# Filtre_PWM1kHz.net
KiCad netlist of a schematic drawn in Altium Designer
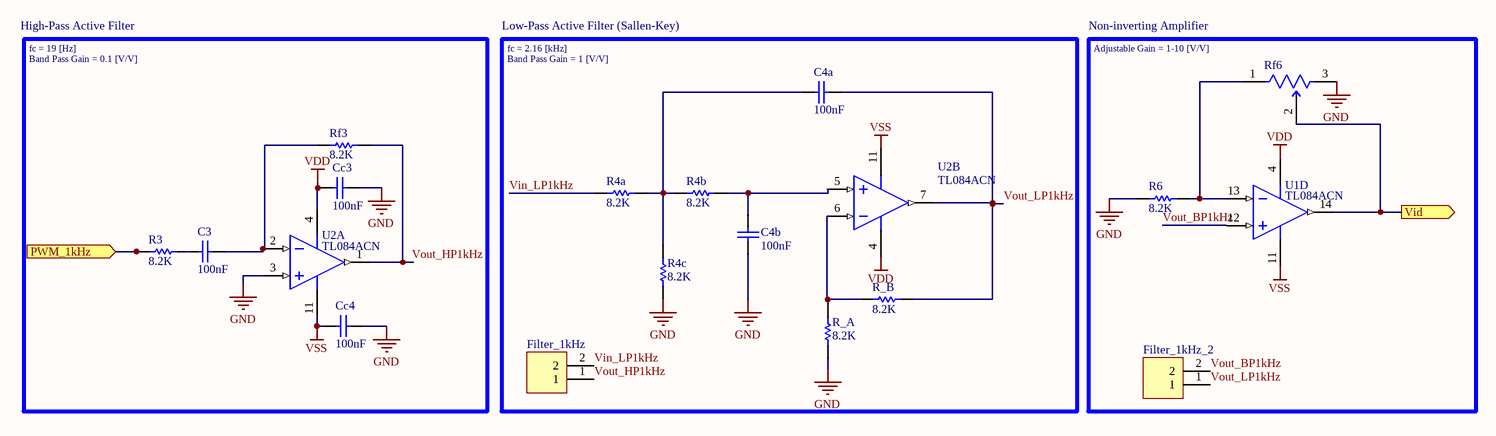
[diagram p0: Filtre_PWM1kHz.SchDoc]

(export (version "E")
  (design (tool "Eeschema 10.0.6"))
  (components
    (comp (ref "C3")
      (value "100nF")
      (footprint "condensateur 0.1uf 100mil")
      (description "Capacitor")
      (fields (field (name "Comment") "Cap") (field (name "PUBLISHER") "Altium Limited"))
      (libsource (lib "signal-generator") (part "Cap"))
    )
    (comp (ref "C4a")
      (value "100nF")
      (footprint "condensateur 0.1uf 100mil")
      (description "Capacitor")
      (fields (field (name "Comment") "Cap") (field (name "PUBLISHER") "Altium Limited"))
      (libsource (lib "signal-generator") (part "Cap"))
    )
    (comp (ref "C4b")
      (value "100nF")
      (footprint "condensateur 0.1uf 100mil")
      (description "Capacitor")
      (fields (field (name "Comment") "Cap") (field (name "PUBLISHER") "Altium Limited"))
      (libsource (lib "signal-generator") (part "Cap"))
    )
    (comp (ref "Cc3")
      (value "100nF")
      (footprint "condensateur 0.1uf 100mil")
      (description "Capacitor")
      (fields (field (name "Comment") "Cap") (field (name "PUBLISHER") "Altium Limited"))
      (libsource (lib "signal-generator") (part "Cap"))
    )
    (comp (ref "Cc4")
      (value "100nF")
      (footprint "condensateur 0.1uf 100mil")
      (description "Capacitor")
      (fields (field (name "Comment") "Cap") (field (name "PUBLISHER") "Altium Limited"))
      (libsource (lib "signal-generator") (part "Cap"))
    )
    (comp (ref "Filter_1kHz")
      (value "Jumper")
      (footprint "Header 2P 100mil")
      (description "CONN HEADER VERT 3POS 2.54MM")
      (fields (field (name "PUBLISHER") "Altium Limited"))
      (libsource (lib "PCB_Alimentation_équipe1") (part "header 2 pin_UL"))
    )
    (comp (ref "Filter_1kHz_2")
      (value "Jumper")
      (footprint "Header 2P 100mil")
      (description "CONN HEADER VERT 3POS 2.54MM")
      (fields (field (name "PUBLISHER") "Altium Limited"))
      (libsource (lib "PCB_Alimentation_équipe1") (part "header 2 pin_UL"))
    )
    (comp (ref "R3")
      (value "8.2K")
      (footprint "Resistor_Axial 0.4")
      (description "Resistor")
      (fields (field (name "Comment") "Res1") (field (name "PUBLISHER") "Altium Limited"))
      (libsource (lib "signal-generator") (part "Res1"))
    )
    (comp (ref "R4a")
      (value "8.2K")
      (footprint "Resistor_Axial 0.4")
      (description "Resistor")
      (fields (field (name "Comment") "Res1") (field (name "PUBLISHER") "Altium Limited"))
      (libsource (lib "signal-generator") (part "Res1"))
    )
    (comp (ref "R4b")
      (value "8.2K")
      (footprint "Resistor_Axial 0.4")
      (description "Resistor")
      (fields (field (name "Comment") "Res1") (field (name "PUBLISHER") "Altium Limited"))
      (libsource (lib "signal-generator") (part "Res1"))
    )
    (comp (ref "R4c")
      (value "8.2K")
      (footprint "Resistor_Axial 0.4")
      (description "Resistor")
      (fields (field (name "Comment") "Res1") (field (name "PUBLISHER") "Altium Limited"))
      (libsource (lib "signal-generator") (part "Res1"))
    )
    (comp (ref "R6")
      (value "8.2K")
      (footprint "Resistor_Axial 0.4")
      (description "Resistor")
      (fields (field (name "Comment") "Res1") (field (name "PUBLISHER") "Altium Limited"))
      (libsource (lib "signal-generator") (part "Res1"))
    )
    (comp (ref "Rf3")
      (value "8.2K")
      (footprint "Resistor_Axial 0.4")
      (description "Resistor")
      (fields (field (name "Comment") "Res1") (field (name "PUBLISHER") "Altium Limited"))
      (libsource (lib "signal-generator") (part "Res1"))
    )
    (comp (ref "Rf6")
      (value "67WR100KLF")
      (footprint "FP-67W-MFG")
      (description "TRIMMER 100K OHM 0.5W PC PIN TOP")
      (fields (field (name "TOLERANCE") "10%"))
      (libsource (lib "Altium Content Vault") (part "a77ee20e32664c43a3a1dd5392b6021"))
    )
    (comp (ref "R_A")
      (value "8.2K")
      (footprint "Resistor_Axial 0.4")
      (description "Resistor")
      (fields (field (name "Comment") "Res1") (field (name "PUBLISHER") "Altium Limited"))
      (libsource (lib "signal-generator") (part "Res1"))
    )
    (comp (ref "R_B")
      (value "8.2K")
      (footprint "Resistor_Axial 0.4")
      (description "Resistor")
      (fields (field (name "Comment") "Res1") (field (name "PUBLISHER") "Altium Limited"))
      (libsource (lib "signal-generator") (part "Res1"))
    )
    (comp (ref "U1")
      (value "TL084ACN")
      (footprint "N0014A")
      (description "JFET-Input Operational Amplifier, 7 to 36 V, 0 to 70 degC, 14-pin DIP (N14), Pb-Free (RoHS)")
      (fields (field (name "MANUFACTURER") "Texas Instruments"))
      (libsource (lib "Altium Content Vault") (part "TI-TLXX4X_MC3403-X14"))
    )
    (comp (ref "U2")
      (value "TL084ACN")
      (footprint "N0014A")
      (description "JFET-Input Operational Amplifier, 7 to 36 V, 0 to 70 degC, 14-pin DIP (N14), Pb-Free (RoHS)")
      (fields (field (name "MANUFACTURER") "Texas Instruments"))
      (libsource (lib "Altium Content Vault") (part "TI-TLXX4X_MC3403-X14"))
    )
  )
  (nets
    (net (code "1") (name "/PWM_1kHz") (class "Default")
      (node (ref "R3") (pin "1") (pinfunction "1_1") (pintype "passive"))
    )
    (net (code "2") (name "/Vid") (class "Default")
      (node (ref "Rf6") (pin "2") (pinfunction "2_2") (pintype "passive"))
      (node (ref "U1") (pin "14") (pinfunction "OUT4_14") (pintype "output"))
    )
    (net (code "3") (name "/Vin_LP1kHz") (class "Default")
      (node (ref "Filter_1kHz") (pin "2") (pinfunction "2_2") (pintype "passive"))
      (node (ref "R4a") (pin "1") (pinfunction "1_1") (pintype "passive"))
    )
    (net (code "4") (name "/Vout_BP1kHz") (class "Default")
      (node (ref "Filter_1kHz_2") (pin "2") (pinfunction "2_2") (pintype "passive"))
      (node (ref "U1") (pin "12") (pinfunction "IN4+_12") (pintype "input"))
    )
    (net (code "5") (name "/Vout_HP1kHz") (class "Default")
      (node (ref "Filter_1kHz") (pin "1") (pinfunction "1_1") (pintype "passive"))
      (node (ref "Rf3") (pin "2") (pinfunction "2_2") (pintype "passive"))
      (node (ref "U2") (pin "1") (pinfunction "OUT1_1") (pintype "output"))
    )
    (net (code "6") (name "/Vout_LP1kHz") (class "Default")
      (node (ref "C4a") (pin "1") (pinfunction "1_1") (pintype "passive"))
      (node (ref "Filter_1kHz_2") (pin "1") (pinfunction "1_1") (pintype "passive"))
      (node (ref "R_B") (pin "2") (pinfunction "2_2") (pintype "passive"))
      (node (ref "U2") (pin "7") (pinfunction "OUT2_7") (pintype "output"))
    )
    (net (code "7") (name "GND") (class "Default")
      (node (ref "C4b") (pin "1") (pinfunction "1_1") (pintype "passive"))
      (node (ref "Cc3") (pin "2") (pinfunction "2_2") (pintype "passive"))
      (node (ref "Cc4") (pin "2") (pinfunction "2_2") (pintype "passive"))
      (node (ref "R4c") (pin "1") (pinfunction "1_1") (pintype "passive"))
      (node (ref "R6") (pin "1") (pinfunction "1_1") (pintype "passive"))
      (node (ref "R_A") (pin "1") (pinfunction "1_1") (pintype "passive"))
      (node (ref "Rf6") (pin "3") (pinfunction "3_3") (pintype "passive"))
      (node (ref "U2") (pin "3") (pinfunction "IN1+_3") (pintype "input"))
    )
    (net (code "8") (name "Net-(C3-Pad1)") (class "Default")
      (node (ref "C3") (pin "1") (pinfunction "1_1") (pintype "passive"))
      (node (ref "R3") (pin "2") (pinfunction "2_2") (pintype "passive"))
    )
    (net (code "9") (name "Net-(C4a-Pad2)") (class "Default")
      (node (ref "C4a") (pin "2") (pinfunction "2_2") (pintype "passive"))
      (node (ref "R4a") (pin "2") (pinfunction "2_2") (pintype "passive"))
      (node (ref "R4b") (pin "1") (pinfunction "1_1") (pintype "passive"))
      (node (ref "R4c") (pin "2") (pinfunction "2_2") (pintype "passive"))
    )
    (net (code "10") (name "Net-(U1D-IN4-)") (class "Default")
      (node (ref "R6") (pin "2") (pinfunction "2_2") (pintype "passive"))
      (node (ref "Rf6") (pin "1") (pinfunction "1_1") (pintype "passive"))
      (node (ref "U1") (pin "13") (pinfunction "IN4-_13") (pintype "input"))
    )
    (net (code "11") (name "Net-(U2A-IN1-)") (class "Default")
      (node (ref "C3") (pin "2") (pinfunction "2_2") (pintype "passive"))
      (node (ref "Rf3") (pin "1") (pinfunction "1_1") (pintype "passive"))
      (node (ref "U2") (pin "2") (pinfunction "IN1-_2") (pintype "input"))
    )
    (net (code "12") (name "Net-(U2B-IN2+)") (class "Default")
      (node (ref "C4b") (pin "2") (pinfunction "2_2") (pintype "passive"))
      (node (ref "R4b") (pin "2") (pinfunction "2_2") (pintype "passive"))
      (node (ref "U2") (pin "5") (pinfunction "IN2+_5") (pintype "input"))
    )
    (net (code "13") (name "Net-(U2B-IN2-)") (class "Default")
      (node (ref "R_A") (pin "2") (pinfunction "2_2") (pintype "passive"))
      (node (ref "R_B") (pin "1") (pinfunction "1_1") (pintype "passive"))
      (node (ref "U2") (pin "6") (pinfunction "IN2-_6") (pintype "input"))
    )
    (net (code "14") (name "VDD") (class "Default")
      (node (ref "Cc3") (pin "1") (pinfunction "1_1") (pintype "passive"))
      (node (ref "U1") (pin "4") (pinfunction "VCC+_4") (pintype "power_in"))
      (node (ref "U2") (pin "4") (pinfunction "VCC+_4") (pintype "power_in"))
    )
    (net (code "15") (name "VSS") (class "Default")
      (node (ref "Cc4") (pin "1") (pinfunction "1_1") (pintype "passive"))
      (node (ref "U1") (pin "11") (pinfunction "VCC-_11") (pintype "power_in"))
      (node (ref "U2") (pin "11") (pinfunction "VCC-_11") (pintype "power_in"))
    )
  )
)
